# 01_-_Peripheral.net
KiCad netlist of a schematic drawn in Altium Designer
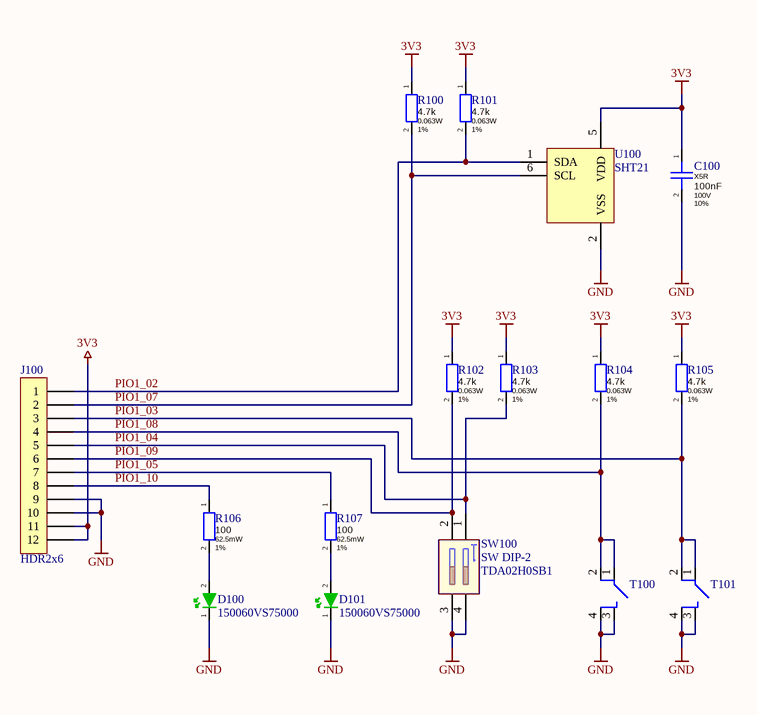
[diagram p0: 01 - Peripheral.SchDoc]

(export (version "E")
  (design (tool "Eeschema 10.0.6"))
  (components
    (comp (ref "C100")
      (value "GRM155R62A104KE14D")
      (footprint "CAPC0402(1005)60_L")
      (description "0.1µF ±10% 100V Ceramic Capacitor X5R 0402 (1005 Metric)")
      (fields
        (field (name "DIELECTRIC") "X5R")
        (field (name "CAPACITANCE") "100nF")
        (field (name "VOLTAGE RATING") "100V")
        (field (name "TOLERANCE") "10%")
        (field (name "MANUFACTURER") "Murata Electronics")
      )
      (libsource (lib "Miromico AG") (part "=Capacitance"))
    )
    (comp (ref "D100")
      (value "150060VS75000")
      (footprint "0603 LED pcb")
      (description "Green 570nm LED Indication - Discrete 2V 0603 (1608 Metric)")
      (fields (field (name "MANUFACTURER") "Wurth Electronics"))
      (libsource (lib "Miromico AG") (part "=Manufacturer Part Number"))
    )
    (comp (ref "D101")
      (value "150060VS75000")
      (footprint "0603 LED pcb")
      (description "Green 570nm LED Indication - Discrete 2V 0603 (1608 Metric)")
      (fields (field (name "MANUFACTURER") "Wurth Electronics"))
      (libsource (lib "Miromico AG") (part "=Manufacturer Part Number"))
    )
    (comp (ref "J100")
      (value "HDR2x6")
      (footprint "HDR2x6")
      (description "2x6 Pin Header, 2.54mm")
      (libsource (lib "Miromico AG") (part "HDR2x6"))
    )
    (comp (ref "R100")
      (value "RMCF0402FT4K70")
      (footprint "RESC0402(1005)_L")
      (description "4.7 kOhms ±1% 0.063W, 1/16W Chip Resistor 0402 (1005 Metric) Automotive AEC-Q200 Thick Film")
      (fields
        (field (name "RESISTANCE") "4.7k")
        (field (name "POWER RATING") "0.063W")
        (field (name "TOLERANCE") "1%")
        (field (name "MANUFACTURER") "Stackpole Electronics Inc")
      )
      (libsource (lib "Miromico AG") (part "=Resistance"))
    )
    (comp (ref "R101")
      (value "RMCF0402FT4K70")
      (footprint "RESC0402(1005)_L")
      (description "4.7 kOhms ±1% 0.063W, 1/16W Chip Resistor 0402 (1005 Metric) Automotive AEC-Q200 Thick Film")
      (fields
        (field (name "RESISTANCE") "4.7k")
        (field (name "POWER RATING") "0.063W")
        (field (name "TOLERANCE") "1%")
        (field (name "MANUFACTURER") "Stackpole Electronics Inc")
      )
      (libsource (lib "Miromico AG") (part "=Resistance"))
    )
    (comp (ref "R102")
      (value "RMCF0402FT4K70")
      (footprint "RESC0402(1005)_L")
      (description "4.7 kOhms ±1% 0.063W, 1/16W Chip Resistor 0402 (1005 Metric) Automotive AEC-Q200 Thick Film")
      (fields
        (field (name "RESISTANCE") "4.7k")
        (field (name "POWER RATING") "0.063W")
        (field (name "TOLERANCE") "1%")
        (field (name "MANUFACTURER") "Stackpole Electronics Inc")
      )
      (libsource (lib "Miromico AG") (part "=Resistance"))
    )
    (comp (ref "R103")
      (value "RMCF0402FT4K70")
      (footprint "RESC0402(1005)_L")
      (description "4.7 kOhms ±1% 0.063W, 1/16W Chip Resistor 0402 (1005 Metric) Automotive AEC-Q200 Thick Film")
      (fields
        (field (name "RESISTANCE") "4.7k")
        (field (name "POWER RATING") "0.063W")
        (field (name "TOLERANCE") "1%")
        (field (name "MANUFACTURER") "Stackpole Electronics Inc")
      )
      (libsource (lib "Miromico AG") (part "=Resistance"))
    )
    (comp (ref "R104")
      (value "RMCF0402FT4K70")
      (footprint "RESC0402(1005)_L")
      (description "4.7 kOhms ±1% 0.063W, 1/16W Chip Resistor 0402 (1005 Metric) Automotive AEC-Q200 Thick Film")
      (fields
        (field (name "RESISTANCE") "4.7k")
        (field (name "POWER RATING") "0.063W")
        (field (name "TOLERANCE") "1%")
        (field (name "MANUFACTURER") "Stackpole Electronics Inc")
      )
      (libsource (lib "Miromico AG") (part "=Resistance"))
    )
    (comp (ref "R105")
      (value "RMCF0402FT4K70")
      (footprint "RESC0402(1005)_L")
      (description "4.7 kOhms ±1% 0.063W, 1/16W Chip Resistor 0402 (1005 Metric) Automotive AEC-Q200 Thick Film")
      (fields
        (field (name "RESISTANCE") "4.7k")
        (field (name "POWER RATING") "0.063W")
        (field (name "TOLERANCE") "1%")
        (field (name "MANUFACTURER") "Stackpole Electronics Inc")
      )
      (libsource (lib "Miromico AG") (part "=Resistance"))
    )
    (comp (ref "R106")
      (value "RC0402FR-07100RL")
      (footprint "RESC0402(1005)_L")
      (description "100 Ohms ±1% 0.063W, 1/16W Chip Resistor 0402 (1005 Metric)  Thick Film")
      (fields
        (field (name "RESISTANCE") "100")
        (field (name "POWER RATING") "62.5mW")
        (field (name "TOLERANCE") "1%")
        (field (name "MANUFACTURER") "Yageo")
      )
      (libsource (lib "Miromico AG") (part "=Resistance"))
    )
    (comp (ref "R107")
      (value "RC0402FR-07100RL")
      (footprint "RESC0402(1005)_L")
      (description "100 Ohms ±1% 0.063W, 1/16W Chip Resistor 0402 (1005 Metric)  Thick Film")
      (fields
        (field (name "RESISTANCE") "100")
        (field (name "POWER RATING") "62.5mW")
        (field (name "TOLERANCE") "1%")
        (field (name "MANUFACTURER") "Yageo")
      )
      (libsource (lib "Miromico AG") (part "=Resistance"))
    )
    (comp (ref "SW100")
      (value "SW DIP-2")
      (footprint "SW_TDA02")
      (description "SWITCH DIP 2POS HALF PITCH 24V")
      (fields
        (field (name "MANUFACTURER_PART_NUMBER") "TDA02H0SB1")
        (field (name "MANUFACTURER") "C&K Components")
      )
      (libsource (lib "Miromico AG") (part "SW DIP-2"))
    )
    (comp (ref "T100")
      (value "PTS645SK43SMTR92LFS")
      (footprint "PTS645SM43SMTR92 LFS - duplicate")
      (description "SWITCH TACTILE SPST-NO 0.05A 12V")
      (fields
        (field (name "MANUFACTURER") "C&K")
        (field (name "MANUFACTURER PART NUMBER") "PTS645SK43SMTR92 LFS")
      )
      (libsource (lib "Miromico AG") (part "PTS645"))
    )
    (comp (ref "T101")
      (value "PTS645SK43SMTR92LFS")
      (footprint "PTS645SM43SMTR92 LFS - duplicate")
      (description "SWITCH TACTILE SPST-NO 0.05A 12V")
      (fields
        (field (name "MANUFACTURER") "C&K")
        (field (name "MANUFACTURER PART NUMBER") "PTS645SK43SMTR92 LFS")
      )
      (libsource (lib "Miromico AG") (part "PTS645"))
    )
    (comp (ref "U100")
      (value "SHT21")
      (footprint "SHT2x_DFN6")
      (description "Hygrometer and Thermometer, I2C Bus")
      (fields (field (name "MANUFACTURER") "SENSIRION"))
      (libsource (lib "Miromico AG") (part "SHT21"))
    )
  )
  (nets
    (net (code "1") (name "/PIO1_02") (class "Default")
      (node (ref "J100") (pin "1") (pinfunction "1_1") (pintype "power_in"))
      (node (ref "R101") (pin "2") (pinfunction "2_2") (pintype "passive"))
      (node (ref "U100") (pin "1") (pinfunction "SDA_1") (pintype "passive"))
    )
    (net (code "2") (name "/PIO1_03") (class "Default")
      (node (ref "J100") (pin "3") (pinfunction "3_3") (pintype "passive"))
      (node (ref "R105") (pin "2") (pinfunction "2_2") (pintype "passive"))
      (node (ref "T101") (pin "1") (pintype "passive"))
      (node (ref "T101") (pin "2") (pintype "passive"))
    )
    (net (code "3") (name "/PIO1_04") (class "Default")
      (node (ref "J100") (pin "5") (pinfunction "5_5") (pintype "passive"))
      (node (ref "R103") (pin "2") (pinfunction "2_2") (pintype "passive"))
      (node (ref "SW100") (pin "1") (pinfunction "A1_1") (pintype "passive"))
    )
    (net (code "4") (name "/PIO1_05") (class "Default")
      (node (ref "J100") (pin "7") (pinfunction "7_7") (pintype "passive"))
      (node (ref "R107") (pin "1") (pinfunction "1_1") (pintype "passive"))
    )
    (net (code "5") (name "/PIO1_07") (class "Default")
      (node (ref "J100") (pin "2") (pinfunction "2_2") (pintype "power_in"))
      (node (ref "R100") (pin "2") (pinfunction "2_2") (pintype "passive"))
      (node (ref "U100") (pin "6") (pinfunction "SCL_6") (pintype "passive"))
    )
    (net (code "6") (name "/PIO1_08") (class "Default")
      (node (ref "J100") (pin "4") (pinfunction "4_4") (pintype "passive"))
      (node (ref "R104") (pin "2") (pinfunction "2_2") (pintype "passive"))
      (node (ref "T100") (pin "1") (pintype "passive"))
      (node (ref "T100") (pin "2") (pintype "passive"))
    )
    (net (code "7") (name "/PIO1_09") (class "Default")
      (node (ref "J100") (pin "6") (pinfunction "6_6") (pintype "passive"))
      (node (ref "R102") (pin "2") (pinfunction "2_2") (pintype "passive"))
      (node (ref "SW100") (pin "2") (pinfunction "A2_2") (pintype "passive"))
    )
    (net (code "8") (name "/PIO1_10") (class "Default")
      (node (ref "J100") (pin "8") (pinfunction "8_8") (pintype "passive"))
      (node (ref "R106") (pin "1") (pinfunction "1_1") (pintype "passive"))
    )
    (net (code "9") (name "3V3") (class "Default")
      (node (ref "C100") (pin "1") (pinfunction "1_1") (pintype "passive"))
      (node (ref "J100") (pin "11") (pinfunction "11_11") (pintype "passive"))
      (node (ref "J100") (pin "12") (pinfunction "12_12") (pintype "passive"))
      (node (ref "R100") (pin "1") (pinfunction "1_1") (pintype "passive"))
      (node (ref "R101") (pin "1") (pinfunction "1_1") (pintype "passive"))
      (node (ref "R102") (pin "1") (pinfunction "1_1") (pintype "passive"))
      (node (ref "R103") (pin "1") (pinfunction "1_1") (pintype "passive"))
      (node (ref "R104") (pin "1") (pinfunction "1_1") (pintype "passive"))
      (node (ref "R105") (pin "1") (pinfunction "1_1") (pintype "passive"))
      (node (ref "U100") (pin "5") (pinfunction "VDD_5") (pintype "passive"))
    )
    (net (code "10") (name "GND") (class "Default")
      (node (ref "C100") (pin "2") (pinfunction "2_2") (pintype "passive"))
      (node (ref "D100") (pin "1") (pinfunction "1_1") (pintype "passive"))
      (node (ref "D101") (pin "1") (pinfunction "1_1") (pintype "passive"))
      (node (ref "J100") (pin "10") (pinfunction "10_10") (pintype "passive"))
      (node (ref "J100") (pin "9") (pinfunction "9_9") (pintype "passive"))
      (node (ref "SW100") (pin "3") (pinfunction "B2_3") (pintype "passive"))
      (node (ref "SW100") (pin "4") (pinfunction "B1_4") (pintype "passive"))
      (node (ref "T100") (pin "3") (pintype "passive"))
      (node (ref "T100") (pin "4") (pintype "passive"))
      (node (ref "T101") (pin "3") (pintype "passive"))
      (node (ref "T101") (pin "4") (pintype "passive"))
      (node (ref "U100") (pin "2") (pinfunction "VSS_2") (pintype "passive"))
    )
    (net (code "11") (name "Net-(D100-Pad2)") (class "Default")
      (node (ref "D100") (pin "2") (pinfunction "2_2") (pintype "passive"))
      (node (ref "R106") (pin "2") (pinfunction "2_2") (pintype "passive"))
    )
    (net (code "12") (name "Net-(D101-Pad2)") (class "Default")
      (node (ref "D101") (pin "2") (pinfunction "2_2") (pintype "passive"))
      (node (ref "R107") (pin "2") (pinfunction "2_2") (pintype "passive"))
    )
  )
)
